# Kameras.net
KiCad netlist of a schematic drawn in Altium Designer
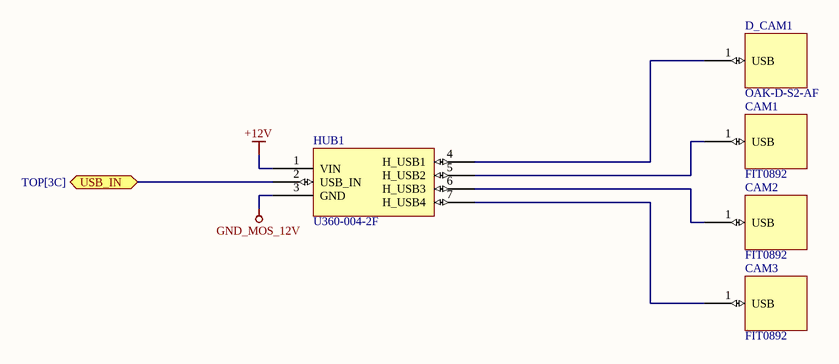
[diagram p0: Kameras.SchDoc]

(export (version "E")
  (design (tool "Eeschema 10.0.6"))
  (components
    (comp (ref "CAM1") (value "FIT0892") (libsource (lib "3D_Scanner") (part "USB Kamera")))
    (comp (ref "CAM2") (value "FIT0892") (libsource (lib "3D_Scanner") (part "USB Kamera")))
    (comp (ref "CAM3") (value "FIT0892") (libsource (lib "3D_Scanner") (part "USB Kamera")))
    (comp (ref "D_CAM1") (value "OAK-D-S2-AF") (libsource (lib "3D_Scanner") (part "Depth Kamera")))
    (comp (ref "HUB1")
      (value "U360-004-2F")
      (description "Interface Modules 4PT USB3.0 SSSPD HUB/CHARGER")
      (libsource (lib "3D_Scanner") (part "USB HUB"))
    )
  )
  (nets
    (net (code "1") (name "+12V") (class "Default")
      (node (ref "HUB1") (pin "1") (pinfunction "VIN_1") (pintype "power_in"))
    )
    (net (code "2") (name "/USB_IN") (class "Default")
      (node (ref "HUB1") (pin "2") (pinfunction "USB_IN_2") (pintype "bidirectional"))
    )
    (net (code "3") (name "GND_MOS_12V") (class "Default")
      (node (ref "HUB1") (pin "3") (pinfunction "GND_3") (pintype "power_in"))
    )
    (net (code "4") (name "Net-(CAM1-USB)") (class "Default")
      (node (ref "CAM1") (pin "1") (pinfunction "USB_1") (pintype "bidirectional"))
      (node (ref "HUB1") (pin "5") (pinfunction "H_USB2_5") (pintype "bidirectional"))
    )
    (net (code "5") (name "Net-(CAM2-USB)") (class "Default")
      (node (ref "CAM2") (pin "1") (pinfunction "USB_1") (pintype "bidirectional"))
      (node (ref "HUB1") (pin "6") (pinfunction "H_USB3_6") (pintype "bidirectional"))
    )
    (net (code "6") (name "Net-(CAM3-USB)") (class "Default")
      (node (ref "CAM3") (pin "1") (pinfunction "USB_1") (pintype "bidirectional"))
      (node (ref "HUB1") (pin "7") (pinfunction "H_USB4_7") (pintype "bidirectional"))
    )
    (net (code "7") (name "Net-(D_CAM1-USB)") (class "Default")
      (node (ref "D_CAM1") (pin "1") (pinfunction "USB_1") (pintype "bidirectional"))
      (node (ref "HUB1") (pin "4") (pinfunction "H_USB1_4") (pintype "bidirectional"))
    )
  )
)
